# SCH_ACC_Register_2021-10-02.net
KiCad netlist of a schematic drawn in EasyEDA
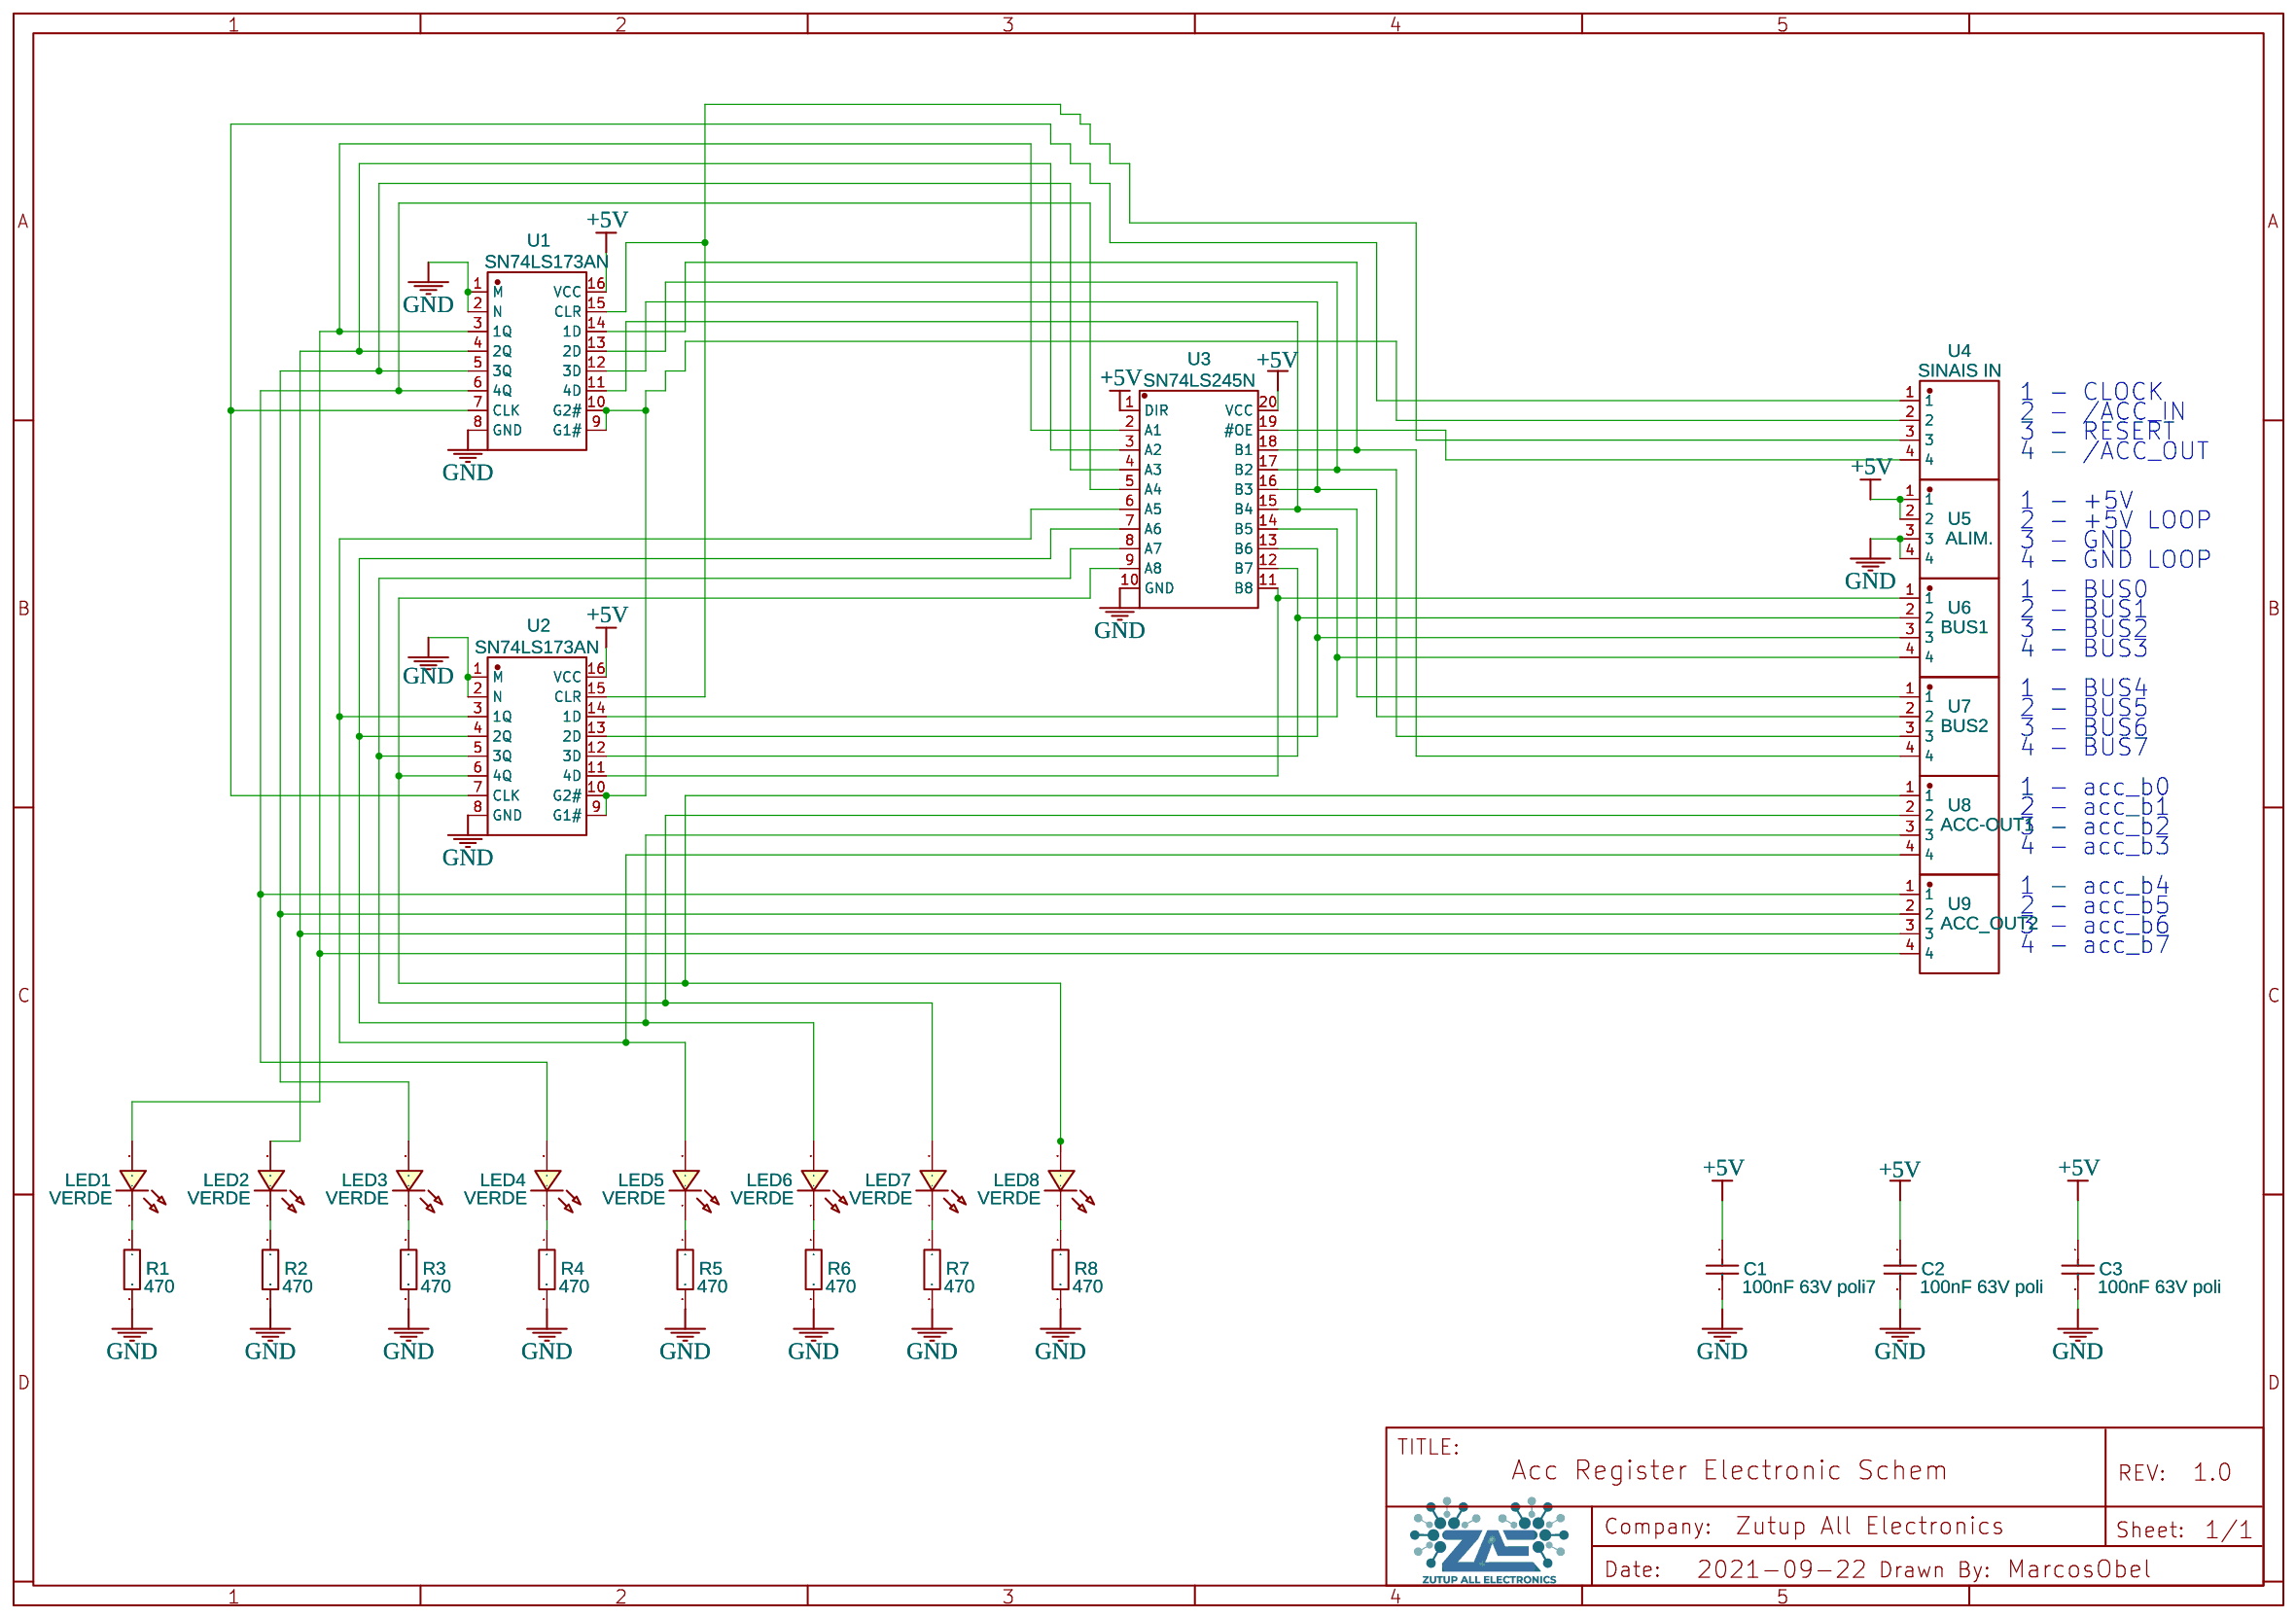
[diagram p0: schematic sheet]

(export (version "E")
  (design (tool "Eeschema 10.0.6"))
  (components
    (comp (ref "C1")
      (value "100nF 63V poli7")
      (fields
        (field (name "BOM_Manufacturer Part") "SR305C105KAR")
        (field (name "BOM_Supplier Part") "C444741")
      )
      (libsource (lib "") (part "SR305C105KAR"))
    )
    (comp (ref "C2")
      (value "100nF 63V poli")
      (fields
        (field (name "BOM_Manufacturer Part") "SR305C105KAR")
        (field (name "BOM_Supplier Part") "C444741")
      )
      (libsource (lib "") (part "SR305C105KAR"))
    )
    (comp (ref "C3")
      (value "100nF 63V poli")
      (fields
        (field (name "BOM_Manufacturer Part") "SR305C105KAR")
        (field (name "BOM_Supplier Part") "C444741")
      )
      (libsource (lib "") (part "SR305C105KAR"))
    )
    (comp (ref "LED1")
      (value "VERDE")
      (fields (field (name "BOM_Manufacturer Part") "264-7GD") (field (name "BOM_Supplier Part") "C605465"))
      (libsource (lib "") (part "264-7GD"))
    )
    (comp (ref "LED2")
      (value "VERDE")
      (fields (field (name "BOM_Manufacturer Part") "264-7GD") (field (name "BOM_Supplier Part") "C605465"))
      (libsource (lib "") (part "264-7GD"))
    )
    (comp (ref "LED3")
      (value "VERDE")
      (fields (field (name "BOM_Manufacturer Part") "264-7GD") (field (name "BOM_Supplier Part") "C605465"))
      (libsource (lib "") (part "264-7GD"))
    )
    (comp (ref "LED4")
      (value "VERDE")
      (fields (field (name "BOM_Manufacturer Part") "264-7GD") (field (name "BOM_Supplier Part") "C605465"))
      (libsource (lib "") (part "264-7GD"))
    )
    (comp (ref "LED5")
      (value "VERDE")
      (fields (field (name "BOM_Manufacturer Part") "264-7GD") (field (name "BOM_Supplier Part") "C605465"))
      (libsource (lib "") (part "264-7GD"))
    )
    (comp (ref "LED6")
      (value "VERDE")
      (fields (field (name "BOM_Manufacturer Part") "264-7GD") (field (name "BOM_Supplier Part") "C605465"))
      (libsource (lib "") (part "264-7GD"))
    )
    (comp (ref "LED7")
      (value "VERDE")
      (fields (field (name "BOM_Manufacturer Part") "264-7GD") (field (name "BOM_Supplier Part") "C605465"))
      (libsource (lib "") (part "264-7GD"))
    )
    (comp (ref "LED8")
      (value "VERDE")
      (fields (field (name "BOM_Manufacturer Part") "264-7GD") (field (name "BOM_Supplier Part") "C605465"))
      (libsource (lib "") (part "264-7GD"))
    )
    (comp (ref "R1")
      (value "470")
      (fields
        (field (name "BOM_Manufacturer Part") "CFR02SJ0823A10")
        (field (name "BOM_Supplier Part") "C69876")
      )
      (libsource (lib "") (part "CFR02SJ0823A10"))
    )
    (comp (ref "R2")
      (value "470")
      (fields
        (field (name "BOM_Manufacturer Part") "CFR02SJ0823A10")
        (field (name "BOM_Supplier Part") "C69876")
      )
      (libsource (lib "") (part "CFR02SJ0823A10"))
    )
    (comp (ref "R3")
      (value "470")
      (fields
        (field (name "BOM_Manufacturer Part") "CFR02SJ0823A10")
        (field (name "BOM_Supplier Part") "C69876")
      )
      (libsource (lib "") (part "CFR02SJ0823A10"))
    )
    (comp (ref "R4")
      (value "470")
      (fields
        (field (name "BOM_Manufacturer Part") "CFR02SJ0823A10")
        (field (name "BOM_Supplier Part") "C69876")
      )
      (libsource (lib "") (part "CFR02SJ0823A10"))
    )
    (comp (ref "R5")
      (value "470")
      (fields
        (field (name "BOM_Manufacturer Part") "CFR02SJ0823A10")
        (field (name "BOM_Supplier Part") "C69876")
      )
      (libsource (lib "") (part "CFR02SJ0823A10"))
    )
    (comp (ref "R6")
      (value "470")
      (fields
        (field (name "BOM_Manufacturer Part") "CFR02SJ0823A10")
        (field (name "BOM_Supplier Part") "C69876")
      )
      (libsource (lib "") (part "CFR02SJ0823A10"))
    )
    (comp (ref "R7")
      (value "470")
      (fields
        (field (name "BOM_Manufacturer Part") "CFR02SJ0823A10")
        (field (name "BOM_Supplier Part") "C69876")
      )
      (libsource (lib "") (part "CFR02SJ0823A10"))
    )
    (comp (ref "R8")
      (value "470")
      (fields
        (field (name "BOM_Manufacturer Part") "CFR02SJ0823A10")
        (field (name "BOM_Supplier Part") "C69876")
      )
      (libsource (lib "") (part "CFR02SJ0823A10"))
    )
    (comp (ref "U1")
      (value "SN74LS173AN")
      (fields (field (name "BOM_Supplier Part") "C1550125"))
      (libsource (lib "") (part "SN74LS173AN"))
    )
    (comp (ref "U2")
      (value "SN74LS173AN")
      (fields (field (name "BOM_Supplier Part") "C1550125"))
      (libsource (lib "") (part "SN74LS173AN"))
    )
    (comp (ref "U3")
      (value "SN74LS245N")
      (fields (field (name "BOM_Supplier Part") "C352966"))
      (libsource (lib "") (part "SN74LS245N"))
    )
    (comp (ref "U4")
      (value "SINAIS IN")
      (fields (field (name "BOM_Manufacturer Part") "171825-4") (field (name "BOM_Supplier Part") "C210162"))
      (libsource (lib "") (part "171825-4"))
    )
    (comp (ref "U5")
      (value "ALIM.")
      (fields (field (name "BOM_Manufacturer Part") "171825-4") (field (name "BOM_Supplier Part") "C210162"))
      (libsource (lib "") (part "171825-4"))
    )
    (comp (ref "U6")
      (value "BUS1")
      (fields (field (name "BOM_Manufacturer Part") "171825-4") (field (name "BOM_Supplier Part") "C210162"))
      (libsource (lib "") (part "171825-4"))
    )
    (comp (ref "U7")
      (value "BUS2")
      (fields (field (name "BOM_Manufacturer Part") "171825-4") (field (name "BOM_Supplier Part") "C210162"))
      (libsource (lib "") (part "171825-4"))
    )
    (comp (ref "U8")
      (value "ACC-OUT1")
      (fields (field (name "BOM_Manufacturer Part") "171825-4") (field (name "BOM_Supplier Part") "C210162"))
      (libsource (lib "") (part "171825-4"))
    )
    (comp (ref "U9")
      (value "ACC_OUT2")
      (fields (field (name "BOM_Manufacturer Part") "171825-4") (field (name "BOM_Supplier Part") "C210162"))
      (libsource (lib "") (part "171825-4"))
    )
  )
  (nets
    (net (code "1") (name "+5V") (class "Default")
      (node (ref "C1") (pin "1") (pinfunction "1_1") (pintype "input"))
      (node (ref "C2") (pin "1") (pinfunction "1_1") (pintype "input"))
      (node (ref "C3") (pin "1") (pinfunction "1_1") (pintype "input"))
      (node (ref "U1") (pin "16") (pinfunction "VCC_16") (pintype "unspecified"))
      (node (ref "U2") (pin "16") (pinfunction "VCC_16") (pintype "unspecified"))
      (node (ref "U3") (pin "1") (pinfunction "DIR_1") (pintype "unspecified"))
      (node (ref "U3") (pin "20") (pinfunction "VCC_20") (pintype "unspecified"))
      (node (ref "U5") (pin "1") (pinfunction "1_1") (pintype "unspecified"))
      (node (ref "U5") (pin "2") (pinfunction "2_2") (pintype "unspecified"))
    )
    (net (code "2") (name "GND") (class "Default")
      (node (ref "C1") (pin "2") (pinfunction "2_2") (pintype "input"))
      (node (ref "C2") (pin "2") (pinfunction "2_2") (pintype "input"))
      (node (ref "C3") (pin "2") (pinfunction "2_2") (pintype "input"))
      (node (ref "R1") (pin "2") (pinfunction "2_2") (pintype "input"))
      (node (ref "R2") (pin "2") (pinfunction "2_2") (pintype "input"))
      (node (ref "R3") (pin "2") (pinfunction "2_2") (pintype "input"))
      (node (ref "R4") (pin "2") (pinfunction "2_2") (pintype "input"))
      (node (ref "R5") (pin "2") (pinfunction "2_2") (pintype "input"))
      (node (ref "R6") (pin "2") (pinfunction "2_2") (pintype "input"))
      (node (ref "R7") (pin "2") (pinfunction "2_2") (pintype "input"))
      (node (ref "R8") (pin "2") (pinfunction "2_2") (pintype "input"))
      (node (ref "U1") (pin "1") (pinfunction "M_1") (pintype "unspecified"))
      (node (ref "U1") (pin "2") (pinfunction "N_2") (pintype "unspecified"))
      (node (ref "U1") (pin "8") (pinfunction "GND_8") (pintype "unspecified"))
      (node (ref "U2") (pin "1") (pinfunction "M_1") (pintype "unspecified"))
      (node (ref "U2") (pin "2") (pinfunction "N_2") (pintype "unspecified"))
      (node (ref "U2") (pin "8") (pinfunction "GND_8") (pintype "unspecified"))
      (node (ref "U3") (pin "10") (pinfunction "GND_10") (pintype "unspecified"))
      (node (ref "U5") (pin "3") (pinfunction "3_3") (pintype "unspecified"))
      (node (ref "U5") (pin "4") (pinfunction "4_4") (pintype "unspecified"))
    )
    (net (code "3") (name "Net-(LED1-+)") (class "Default")
      (node (ref "LED1") (pin "2") (pinfunction "+_2") (pintype "unspecified"))
      (node (ref "U1") (pin "3") (pinfunction "1Q_3") (pintype "unspecified"))
      (node (ref "U3") (pin "2") (pinfunction "A1_2") (pintype "unspecified"))
      (node (ref "U9") (pin "4") (pinfunction "4_4") (pintype "unspecified"))
    )
    (net (code "4") (name "Net-(LED1--)") (class "Default")
      (node (ref "LED1") (pin "1") (pinfunction "-_1") (pintype "unspecified"))
      (node (ref "R1") (pin "1") (pinfunction "1_1") (pintype "input"))
    )
    (net (code "5") (name "Net-(LED2-+)") (class "Default")
      (node (ref "LED2") (pin "2") (pinfunction "+_2") (pintype "unspecified"))
      (node (ref "U1") (pin "4") (pinfunction "2Q_4") (pintype "unspecified"))
      (node (ref "U3") (pin "3") (pinfunction "A2_3") (pintype "unspecified"))
      (node (ref "U9") (pin "3") (pinfunction "3_3") (pintype "unspecified"))
    )
    (net (code "6") (name "Net-(LED2--)") (class "Default")
      (node (ref "LED2") (pin "1") (pinfunction "-_1") (pintype "unspecified"))
      (node (ref "R2") (pin "1") (pinfunction "1_1") (pintype "input"))
    )
    (net (code "7") (name "Net-(LED3-+)") (class "Default")
      (node (ref "LED3") (pin "2") (pinfunction "+_2") (pintype "unspecified"))
      (node (ref "U1") (pin "5") (pinfunction "3Q_5") (pintype "unspecified"))
      (node (ref "U3") (pin "4") (pinfunction "A3_4") (pintype "unspecified"))
      (node (ref "U9") (pin "2") (pinfunction "2_2") (pintype "unspecified"))
    )
    (net (code "8") (name "Net-(LED3--)") (class "Default")
      (node (ref "LED3") (pin "1") (pinfunction "-_1") (pintype "unspecified"))
      (node (ref "R3") (pin "1") (pinfunction "1_1") (pintype "input"))
    )
    (net (code "9") (name "Net-(LED4-+)") (class "Default")
      (node (ref "LED4") (pin "2") (pinfunction "+_2") (pintype "unspecified"))
      (node (ref "U1") (pin "6") (pinfunction "4Q_6") (pintype "unspecified"))
      (node (ref "U3") (pin "5") (pinfunction "A4_5") (pintype "unspecified"))
      (node (ref "U9") (pin "1") (pinfunction "1_1") (pintype "unspecified"))
    )
    (net (code "10") (name "Net-(LED4--)") (class "Default")
      (node (ref "LED4") (pin "1") (pinfunction "-_1") (pintype "unspecified"))
      (node (ref "R4") (pin "1") (pinfunction "1_1") (pintype "input"))
    )
    (net (code "11") (name "Net-(LED5-+)") (class "Default")
      (node (ref "LED5") (pin "2") (pinfunction "+_2") (pintype "unspecified"))
      (node (ref "U2") (pin "3") (pinfunction "1Q_3") (pintype "unspecified"))
      (node (ref "U3") (pin "6") (pinfunction "A5_6") (pintype "unspecified"))
      (node (ref "U8") (pin "4") (pinfunction "4_4") (pintype "unspecified"))
    )
    (net (code "12") (name "Net-(LED5--)") (class "Default")
      (node (ref "LED5") (pin "1") (pinfunction "-_1") (pintype "unspecified"))
      (node (ref "R5") (pin "1") (pinfunction "1_1") (pintype "input"))
    )
    (net (code "13") (name "Net-(LED6-+)") (class "Default")
      (node (ref "LED6") (pin "2") (pinfunction "+_2") (pintype "unspecified"))
      (node (ref "U2") (pin "4") (pinfunction "2Q_4") (pintype "unspecified"))
      (node (ref "U3") (pin "7") (pinfunction "A6_7") (pintype "unspecified"))
      (node (ref "U8") (pin "3") (pinfunction "3_3") (pintype "unspecified"))
    )
    (net (code "14") (name "Net-(LED6--)") (class "Default")
      (node (ref "LED6") (pin "1") (pinfunction "-_1") (pintype "unspecified"))
      (node (ref "R6") (pin "1") (pinfunction "1_1") (pintype "input"))
    )
    (net (code "15") (name "Net-(LED7-+)") (class "Default")
      (node (ref "LED7") (pin "2") (pinfunction "+_2") (pintype "unspecified"))
      (node (ref "U2") (pin "5") (pinfunction "3Q_5") (pintype "unspecified"))
      (node (ref "U3") (pin "8") (pinfunction "A7_8") (pintype "unspecified"))
      (node (ref "U8") (pin "2") (pinfunction "2_2") (pintype "unspecified"))
    )
    (net (code "16") (name "Net-(LED7--)") (class "Default")
      (node (ref "LED7") (pin "1") (pinfunction "-_1") (pintype "unspecified"))
      (node (ref "R7") (pin "1") (pinfunction "1_1") (pintype "input"))
    )
    (net (code "17") (name "Net-(LED8-+)") (class "Default")
      (node (ref "LED8") (pin "2") (pinfunction "+_2") (pintype "unspecified"))
      (node (ref "U2") (pin "6") (pinfunction "4Q_6") (pintype "unspecified"))
      (node (ref "U3") (pin "9") (pinfunction "A8_9") (pintype "unspecified"))
      (node (ref "U8") (pin "1") (pinfunction "1_1") (pintype "unspecified"))
    )
    (net (code "18") (name "Net-(LED8--)") (class "Default")
      (node (ref "LED8") (pin "1") (pinfunction "-_1") (pintype "unspecified"))
      (node (ref "R8") (pin "1") (pinfunction "1_1") (pintype "input"))
    )
    (net (code "19") (name "Net-(U1-1D)") (class "Default")
      (node (ref "U1") (pin "14") (pinfunction "1D_14") (pintype "unspecified"))
      (node (ref "U3") (pin "18") (pinfunction "B1_18") (pintype "unspecified"))
      (node (ref "U7") (pin "4") (pinfunction "4_4") (pintype "unspecified"))
    )
    (net (code "20") (name "Net-(U1-2D)") (class "Default")
      (node (ref "U1") (pin "13") (pinfunction "2D_13") (pintype "unspecified"))
      (node (ref "U3") (pin "17") (pinfunction "B2_17") (pintype "unspecified"))
      (node (ref "U7") (pin "3") (pinfunction "3_3") (pintype "unspecified"))
    )
    (net (code "21") (name "Net-(U1-3D)") (class "Default")
      (node (ref "U1") (pin "12") (pinfunction "3D_12") (pintype "unspecified"))
      (node (ref "U3") (pin "16") (pinfunction "B3_16") (pintype "unspecified"))
      (node (ref "U7") (pin "2") (pinfunction "2_2") (pintype "unspecified"))
    )
    (net (code "22") (name "Net-(U1-4D)") (class "Default")
      (node (ref "U1") (pin "11") (pinfunction "4D_11") (pintype "unspecified"))
      (node (ref "U3") (pin "15") (pinfunction "B4_15") (pintype "unspecified"))
      (node (ref "U7") (pin "1") (pinfunction "1_1") (pintype "unspecified"))
    )
    (net (code "23") (name "Net-(U1-CLK)") (class "Default")
      (node (ref "U1") (pin "7") (pinfunction "CLK_7") (pintype "unspecified"))
      (node (ref "U2") (pin "7") (pinfunction "CLK_7") (pintype "unspecified"))
      (node (ref "U4") (pin "1") (pinfunction "1_1") (pintype "unspecified"))
    )
    (net (code "24") (name "Net-(U1-CLR)") (class "Default")
      (node (ref "U1") (pin "15") (pinfunction "CLR_15") (pintype "unspecified"))
      (node (ref "U2") (pin "15") (pinfunction "CLR_15") (pintype "unspecified"))
      (node (ref "U4") (pin "3") (pinfunction "3_3") (pintype "unspecified"))
    )
    (net (code "25") (name "Net-(U1-G1#)") (class "Default")
      (node (ref "U1") (pin "10") (pinfunction "G2#_10") (pintype "unspecified"))
      (node (ref "U1") (pin "9") (pinfunction "G1#_9") (pintype "unspecified"))
      (node (ref "U2") (pin "10") (pinfunction "G2#_10") (pintype "unspecified"))
      (node (ref "U2") (pin "9") (pinfunction "G1#_9") (pintype "unspecified"))
      (node (ref "U4") (pin "2") (pinfunction "2_2") (pintype "unspecified"))
    )
    (net (code "26") (name "Net-(U2-1D)") (class "Default")
      (node (ref "U2") (pin "14") (pinfunction "1D_14") (pintype "unspecified"))
      (node (ref "U3") (pin "14") (pinfunction "B5_14") (pintype "unspecified"))
      (node (ref "U6") (pin "4") (pinfunction "4_4") (pintype "unspecified"))
    )
    (net (code "27") (name "Net-(U2-2D)") (class "Default")
      (node (ref "U2") (pin "13") (pinfunction "2D_13") (pintype "unspecified"))
      (node (ref "U3") (pin "13") (pinfunction "B6_13") (pintype "unspecified"))
      (node (ref "U6") (pin "3") (pinfunction "3_3") (pintype "unspecified"))
    )
    (net (code "28") (name "Net-(U2-3D)") (class "Default")
      (node (ref "U2") (pin "12") (pinfunction "3D_12") (pintype "unspecified"))
      (node (ref "U3") (pin "12") (pinfunction "B7_12") (pintype "unspecified"))
      (node (ref "U6") (pin "2") (pinfunction "2_2") (pintype "unspecified"))
    )
    (net (code "29") (name "Net-(U2-4D)") (class "Default")
      (node (ref "U2") (pin "11") (pinfunction "4D_11") (pintype "unspecified"))
      (node (ref "U3") (pin "11") (pinfunction "B8_11") (pintype "unspecified"))
      (node (ref "U6") (pin "1") (pinfunction "1_1") (pintype "unspecified"))
    )
    (net (code "30") (name "Net-(U3-#OE)") (class "Default")
      (node (ref "U3") (pin "19") (pinfunction "#OE_19") (pintype "unspecified"))
      (node (ref "U4") (pin "4") (pinfunction "4_4") (pintype "unspecified"))
    )
  )
)
